# FPGA_NES_controller.net
KiCad netlist of a schematic drawn in EAGLE
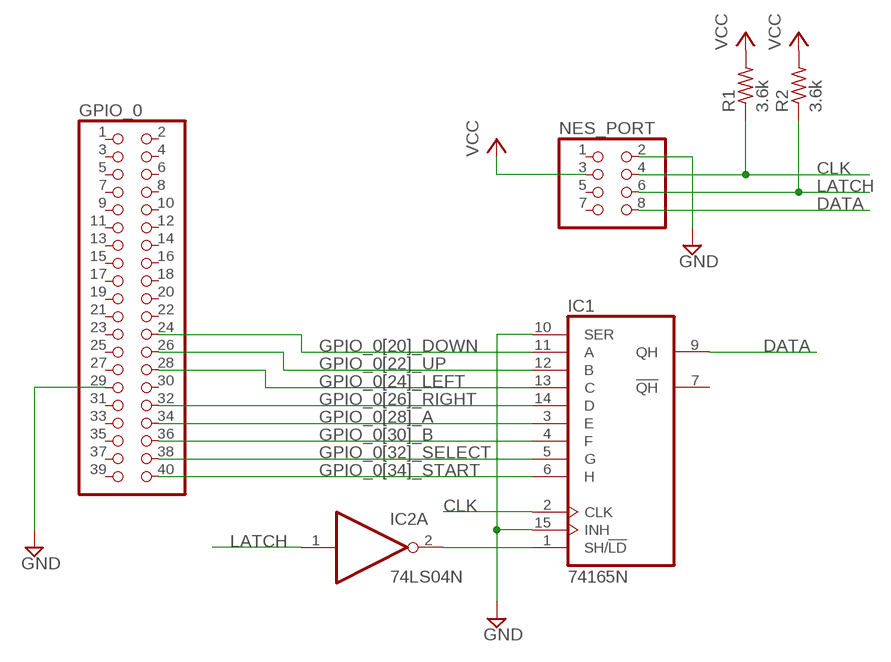
[diagram p0: schematic, sheet 1]

(export (version "E")
  (design (tool "Eeschema 10.0.6"))
  (components
    (comp (ref "GPIO_0")
      (value "PINHD-2X20")
      (footprint "eagle-import:2X20")
      (libsource (lib "eagle-import") (part "PINHD-2X20"))
    )
    (comp (ref "IC1")
      (value "74165N")
      (footprint "eagle-import:DIL16")
      (libsource (lib "eagle-import") (part "74165N"))
    )
    (comp (ref "IC2")
      (value "74LS04N")
      (footprint "eagle-import:DIL14")
      (libsource (lib "eagle-import") (part "7404NLS"))
    )
    (comp (ref "NES_PORT")
      (value "PINHD-2X4")
      (footprint "eagle-import:2X04")
      (libsource (lib "eagle-import") (part "PINHD-2X4"))
    )
    (comp (ref "R1")
      (value "3.6k")
      (footprint "eagle-import:V526-0")
      (libsource (lib "eagle-import") (part "R-US_V526-0"))
    )
    (comp (ref "R2")
      (value "3.6k")
      (footprint "eagle-import:V526-0")
      (libsource (lib "eagle-import") (part "R-US_V526-0"))
    )
  )
  (nets
    (net (code "1") (name "/CLK") (class "Default")
      (node (ref "IC1") (pin "2") (pinfunction "CLK_2") (pintype "input"))
      (node (ref "NES_PORT") (pin "4") (pinfunction "4_4") (pintype "passive"))
      (node (ref "R1") (pin "1") (pinfunction "1_1") (pintype "passive"))
    )
    (net (code "2") (name "/DATA") (class "Default")
      (node (ref "IC1") (pin "9") (pinfunction "QH_9") (pintype "output"))
      (node (ref "NES_PORT") (pin "8") (pinfunction "8_8") (pintype "passive"))
    )
    (net (code "3") (name "/GPIO_0[20]_DOWN") (class "Default")
      (node (ref "GPIO_0") (pin "24") (pinfunction "24_24") (pintype "passive"))
      (node (ref "IC1") (pin "11") (pinfunction "A_11") (pintype "input"))
    )
    (net (code "4") (name "/GPIO_0[22]_UP") (class "Default")
      (node (ref "GPIO_0") (pin "26") (pinfunction "26_26") (pintype "passive"))
      (node (ref "IC1") (pin "12") (pinfunction "B_12") (pintype "input"))
    )
    (net (code "5") (name "/GPIO_0[24]_LEFT") (class "Default")
      (node (ref "GPIO_0") (pin "28") (pinfunction "28_28") (pintype "passive"))
      (node (ref "IC1") (pin "13") (pinfunction "C_13") (pintype "input"))
    )
    (net (code "6") (name "/GPIO_0[26]_RIGHT") (class "Default")
      (node (ref "GPIO_0") (pin "32") (pinfunction "32_32") (pintype "passive"))
      (node (ref "IC1") (pin "14") (pinfunction "D_14") (pintype "input"))
    )
    (net (code "7") (name "/GPIO_0[28]_A") (class "Default")
      (node (ref "GPIO_0") (pin "34") (pinfunction "34_34") (pintype "passive"))
      (node (ref "IC1") (pin "3") (pinfunction "E_3") (pintype "input"))
    )
    (net (code "8") (name "/GPIO_0[30]_B") (class "Default")
      (node (ref "GPIO_0") (pin "36") (pinfunction "36_36") (pintype "passive"))
      (node (ref "IC1") (pin "4") (pinfunction "F_4") (pintype "input"))
    )
    (net (code "9") (name "/GPIO_0[32]_SELECT") (class "Default")
      (node (ref "GPIO_0") (pin "38") (pinfunction "38_38") (pintype "passive"))
      (node (ref "IC1") (pin "5") (pinfunction "G_5") (pintype "input"))
    )
    (net (code "10") (name "/GPIO_0[34]_START") (class "Default")
      (node (ref "GPIO_0") (pin "40") (pinfunction "40_40") (pintype "passive"))
      (node (ref "IC1") (pin "6") (pinfunction "H_6") (pintype "input"))
    )
    (net (code "11") (name "/LATCH") (class "Default")
      (node (ref "IC2") (pin "1") (pinfunction "I_1") (pintype "input"))
      (node (ref "NES_PORT") (pin "6") (pinfunction "6_6") (pintype "passive"))
      (node (ref "R2") (pin "1") (pinfunction "1_1") (pintype "passive"))
    )
    (net (code "12") (name "GND") (class "Default")
      (node (ref "GPIO_0") (pin "29") (pinfunction "29_29") (pintype "passive"))
      (node (ref "IC1") (pin "10") (pinfunction "SER_10") (pintype "input"))
      (node (ref "IC1") (pin "15") (pinfunction "INH_15") (pintype "input"))
      (node (ref "NES_PORT") (pin "2") (pinfunction "2_2") (pintype "passive"))
    )
    (net (code "13") (name "Net-(IC1A-SH{slash}~{LD})") (class "Default")
      (node (ref "IC1") (pin "1") (pinfunction "SH/~{LD}_1") (pintype "input"))
      (node (ref "IC2") (pin "2") (pinfunction "O_2") (pintype "output"))
    )
    (net (code "14") (name "VCC") (class "Default")
      (node (ref "NES_PORT") (pin "3") (pinfunction "3_3") (pintype "passive"))
      (node (ref "R1") (pin "2") (pinfunction "2_2") (pintype "passive"))
      (node (ref "R2") (pin "2") (pinfunction "2_2") (pintype "passive"))
    )
    (net (code "15") (name "unconnected-(GPIO_0-Pad1)") (class "Default")
      (node (ref "GPIO_0") (pin "1") (pinfunction "1_1") (pintype "passive"))
    )
    (net (code "16") (name "unconnected-(GPIO_0-Pad2)") (class "Default")
      (node (ref "GPIO_0") (pin "2") (pinfunction "2_2") (pintype "passive"))
    )
    (net (code "17") (name "unconnected-(GPIO_0-Pad3)") (class "Default")
      (node (ref "GPIO_0") (pin "3") (pinfunction "3_3") (pintype "passive"))
    )
    (net (code "18") (name "unconnected-(GPIO_0-Pad4)") (class "Default")
      (node (ref "GPIO_0") (pin "4") (pinfunction "4_4") (pintype "passive"))
    )
    (net (code "19") (name "unconnected-(GPIO_0-Pad5)") (class "Default")
      (node (ref "GPIO_0") (pin "5") (pinfunction "5_5") (pintype "passive"))
    )
    (net (code "20") (name "unconnected-(GPIO_0-Pad6)") (class "Default")
      (node (ref "GPIO_0") (pin "6") (pinfunction "6_6") (pintype "passive"))
    )
    (net (code "21") (name "unconnected-(GPIO_0-Pad7)") (class "Default")
      (node (ref "GPIO_0") (pin "7") (pinfunction "7_7") (pintype "passive"))
    )
    (net (code "22") (name "unconnected-(GPIO_0-Pad8)") (class "Default")
      (node (ref "GPIO_0") (pin "8") (pinfunction "8_8") (pintype "passive"))
    )
    (net (code "23") (name "unconnected-(GPIO_0-Pad9)") (class "Default")
      (node (ref "GPIO_0") (pin "9") (pinfunction "9_9") (pintype "passive"))
    )
    (net (code "24") (name "unconnected-(GPIO_0-Pad10)") (class "Default")
      (node (ref "GPIO_0") (pin "10") (pinfunction "10_10") (pintype "passive"))
    )
    (net (code "25") (name "unconnected-(GPIO_0-Pad11)") (class "Default")
      (node (ref "GPIO_0") (pin "11") (pinfunction "11_11") (pintype "passive"))
    )
    (net (code "26") (name "unconnected-(GPIO_0-Pad12)") (class "Default")
      (node (ref "GPIO_0") (pin "12") (pinfunction "12_12") (pintype "passive"))
    )
    (net (code "27") (name "unconnected-(GPIO_0-Pad13)") (class "Default")
      (node (ref "GPIO_0") (pin "13") (pinfunction "13_13") (pintype "passive"))
    )
    (net (code "28") (name "unconnected-(GPIO_0-Pad14)") (class "Default")
      (node (ref "GPIO_0") (pin "14") (pinfunction "14_14") (pintype "passive"))
    )
    (net (code "29") (name "unconnected-(GPIO_0-Pad15)") (class "Default")
      (node (ref "GPIO_0") (pin "15") (pinfunction "15_15") (pintype "passive"))
    )
    (net (code "30") (name "unconnected-(GPIO_0-Pad16)") (class "Default")
      (node (ref "GPIO_0") (pin "16") (pinfunction "16_16") (pintype "passive"))
    )
    (net (code "31") (name "unconnected-(GPIO_0-Pad17)") (class "Default")
      (node (ref "GPIO_0") (pin "17") (pinfunction "17_17") (pintype "passive"))
    )
    (net (code "32") (name "unconnected-(GPIO_0-Pad18)") (class "Default")
      (node (ref "GPIO_0") (pin "18") (pinfunction "18_18") (pintype "passive"))
    )
    (net (code "33") (name "unconnected-(GPIO_0-Pad19)") (class "Default")
      (node (ref "GPIO_0") (pin "19") (pinfunction "19_19") (pintype "passive"))
    )
    (net (code "34") (name "unconnected-(GPIO_0-Pad20)") (class "Default")
      (node (ref "GPIO_0") (pin "20") (pinfunction "20_20") (pintype "passive"))
    )
    (net (code "35") (name "unconnected-(GPIO_0-Pad21)") (class "Default")
      (node (ref "GPIO_0") (pin "21") (pinfunction "21_21") (pintype "passive"))
    )
    (net (code "36") (name "unconnected-(GPIO_0-Pad22)") (class "Default")
      (node (ref "GPIO_0") (pin "22") (pinfunction "22_22") (pintype "passive"))
    )
    (net (code "37") (name "unconnected-(GPIO_0-Pad23)") (class "Default")
      (node (ref "GPIO_0") (pin "23") (pinfunction "23_23") (pintype "passive"))
    )
    (net (code "38") (name "unconnected-(GPIO_0-Pad25)") (class "Default")
      (node (ref "GPIO_0") (pin "25") (pinfunction "25_25") (pintype "passive"))
    )
    (net (code "39") (name "unconnected-(GPIO_0-Pad27)") (class "Default")
      (node (ref "GPIO_0") (pin "27") (pinfunction "27_27") (pintype "passive"))
    )
    (net (code "40") (name "unconnected-(GPIO_0-Pad30)") (class "Default")
      (node (ref "GPIO_0") (pin "30") (pinfunction "30_30") (pintype "passive"))
    )
    (net (code "41") (name "unconnected-(GPIO_0-Pad31)") (class "Default")
      (node (ref "GPIO_0") (pin "31") (pinfunction "31_31") (pintype "passive"))
    )
    (net (code "42") (name "unconnected-(GPIO_0-Pad33)") (class "Default")
      (node (ref "GPIO_0") (pin "33") (pinfunction "33_33") (pintype "passive"))
    )
    (net (code "43") (name "unconnected-(GPIO_0-Pad35)") (class "Default")
      (node (ref "GPIO_0") (pin "35") (pinfunction "35_35") (pintype "passive"))
    )
    (net (code "44") (name "unconnected-(GPIO_0-Pad37)") (class "Default")
      (node (ref "GPIO_0") (pin "37") (pinfunction "37_37") (pintype "passive"))
    )
    (net (code "45") (name "unconnected-(GPIO_0-Pad39)") (class "Default")
      (node (ref "GPIO_0") (pin "39") (pinfunction "39_39") (pintype "passive"))
    )
    (net (code "46") (name "unconnected-(IC1A-~{QH}-Pad7)") (class "Default")
      (node (ref "IC1") (pin "7") (pinfunction "~{QH}_7") (pintype "output"))
    )
    (net (code "47") (name "unconnected-(NES_PORT-Pad1)") (class "Default")
      (node (ref "NES_PORT") (pin "1") (pinfunction "1_1") (pintype "passive"))
    )
    (net (code "48") (name "unconnected-(NES_PORT-Pad5)") (class "Default")
      (node (ref "NES_PORT") (pin "5") (pinfunction "5_5") (pintype "passive"))
    )
    (net (code "49") (name "unconnected-(NES_PORT-Pad7)") (class "Default")
      (node (ref "NES_PORT") (pin "7") (pinfunction "7_7") (pintype "passive"))
    )
  )
)
